# LIXIE_II.net
KiCad netlist of a schematic drawn in EAGLE
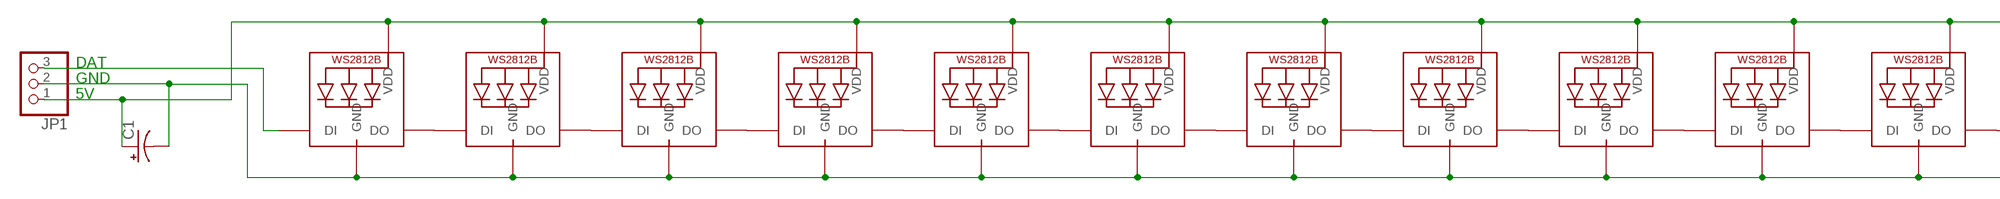
[diagram p0: schematic, sheet 1, part 1 of 2]
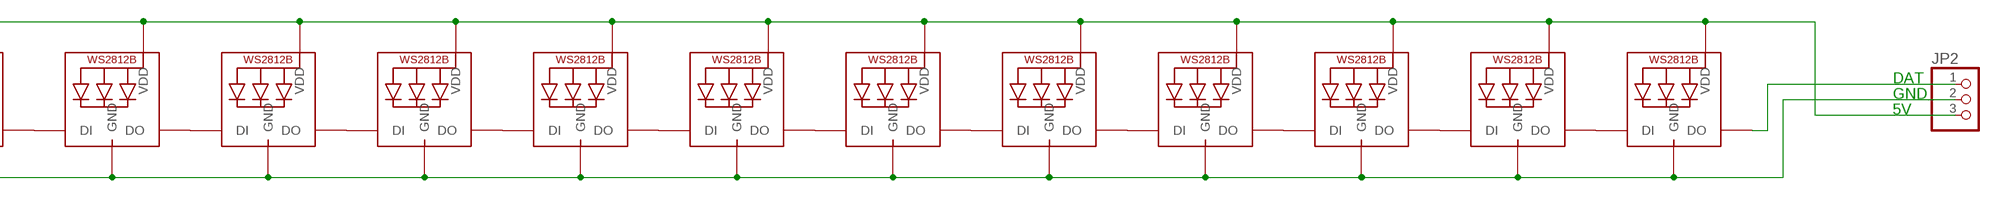
[diagram p1: schematic, sheet 1, part 2 of 2]

(export (version "E")
  (design (tool "Eeschema 10.0.6"))
  (components
    (comp (ref "C1")
      (value "CPOL-USE5-10.5")
      (footprint "eagle-import:E5-10,5")
      (libsource (lib "eagle-import") (part "CPOL-USE5-10.5"))
    )
    (comp (ref "JP1")
      (value "PINHD-1X3")
      (footprint "eagle-import:1X03")
      (libsource (lib "eagle-import") (part "PINHD-1X3"))
    )
    (comp (ref "JP2")
      (value "PINHD-1X3")
      (footprint "eagle-import:1X03")
      (libsource (lib "eagle-import") (part "PINHD-1X3"))
    )
    (comp (ref "LED1")
      (value "WS2812B_5050N")
      (footprint "eagle-import:WS2812B-NARROW")
      (libsource (lib "eagle-import") (part "WS2812B_5050N"))
    )
    (comp (ref "LED2")
      (value "WS2812B_5050N")
      (footprint "eagle-import:WS2812B-NARROW")
      (libsource (lib "eagle-import") (part "WS2812B_5050N"))
    )
    (comp (ref "LED3")
      (value "WS2812B_5050N")
      (footprint "eagle-import:WS2812B-NARROW")
      (libsource (lib "eagle-import") (part "WS2812B_5050N"))
    )
    (comp (ref "LED4")
      (value "WS2812B_5050N")
      (footprint "eagle-import:WS2812B-NARROW")
      (libsource (lib "eagle-import") (part "WS2812B_5050N"))
    )
    (comp (ref "LED5")
      (value "WS2812B_5050N")
      (footprint "eagle-import:WS2812B-NARROW")
      (libsource (lib "eagle-import") (part "WS2812B_5050N"))
    )
    (comp (ref "LED6")
      (value "WS2812B_5050N")
      (footprint "eagle-import:WS2812B-NARROW")
      (libsource (lib "eagle-import") (part "WS2812B_5050N"))
    )
    (comp (ref "LED7")
      (value "WS2812B_5050N")
      (footprint "eagle-import:WS2812B-NARROW")
      (libsource (lib "eagle-import") (part "WS2812B_5050N"))
    )
    (comp (ref "LED8")
      (value "WS2812B_5050N")
      (footprint "eagle-import:WS2812B-NARROW")
      (libsource (lib "eagle-import") (part "WS2812B_5050N"))
    )
    (comp (ref "LED9")
      (value "WS2812B_5050N")
      (footprint "eagle-import:WS2812B-NARROW")
      (libsource (lib "eagle-import") (part "WS2812B_5050N"))
    )
    (comp (ref "LED10")
      (value "WS2812B_5050N")
      (footprint "eagle-import:WS2812B-NARROW")
      (libsource (lib "eagle-import") (part "WS2812B_5050N"))
    )
    (comp (ref "LED11")
      (value "WS2812B_5050N")
      (footprint "eagle-import:WS2812B-NARROW")
      (libsource (lib "eagle-import") (part "WS2812B_5050N"))
    )
    (comp (ref "LED12")
      (value "WS2812B_5050N")
      (footprint "eagle-import:WS2812B-NARROW")
      (libsource (lib "eagle-import") (part "WS2812B_5050N"))
    )
    (comp (ref "LED13")
      (value "WS2812B_5050N")
      (footprint "eagle-import:WS2812B-NARROW")
      (libsource (lib "eagle-import") (part "WS2812B_5050N"))
    )
    (comp (ref "LED14")
      (value "WS2812B_5050N")
      (footprint "eagle-import:WS2812B-NARROW")
      (libsource (lib "eagle-import") (part "WS2812B_5050N"))
    )
    (comp (ref "LED15")
      (value "WS2812B_5050N")
      (footprint "eagle-import:WS2812B-NARROW")
      (libsource (lib "eagle-import") (part "WS2812B_5050N"))
    )
    (comp (ref "LED16")
      (value "WS2812B_5050N")
      (footprint "eagle-import:WS2812B-NARROW")
      (libsource (lib "eagle-import") (part "WS2812B_5050N"))
    )
    (comp (ref "LED17")
      (value "WS2812B_5050N")
      (footprint "eagle-import:WS2812B-NARROW")
      (libsource (lib "eagle-import") (part "WS2812B_5050N"))
    )
    (comp (ref "LED18")
      (value "WS2812B_5050N")
      (footprint "eagle-import:WS2812B-NARROW")
      (libsource (lib "eagle-import") (part "WS2812B_5050N"))
    )
    (comp (ref "LED19")
      (value "WS2812B_5050N")
      (footprint "eagle-import:WS2812B-NARROW")
      (libsource (lib "eagle-import") (part "WS2812B_5050N"))
    )
    (comp (ref "LED20")
      (value "WS2812B_5050N")
      (footprint "eagle-import:WS2812B-NARROW")
      (libsource (lib "eagle-import") (part "WS2812B_5050N"))
    )
    (comp (ref "LED21")
      (value "WS2812B_5050N")
      (footprint "eagle-import:WS2812B-NARROW")
      (libsource (lib "eagle-import") (part "WS2812B_5050N"))
    )
    (comp (ref "LED22")
      (value "WS2812B_5050N")
      (footprint "eagle-import:WS2812B-NARROW")
      (libsource (lib "eagle-import") (part "WS2812B_5050N"))
    )
  )
  (nets
    (net (code "1") (name "Net-(LED1-DI)") (class "Default")
      (node (ref "JP1") (pin "3") (pinfunction "3_3") (pintype "passive"))
      (node (ref "LED1") (pin "4-DIN") (pinfunction "DI_4-DIN") (pintype "input"))
    )
    (net (code "2") (name "Net-(LED1-DO)") (class "Default")
      (node (ref "LED1") (pin "2-DOUT") (pinfunction "DO_2-DOUT") (pintype "output"))
      (node (ref "LED2") (pin "4-DIN") (pinfunction "DI_4-DIN") (pintype "input"))
    )
    (net (code "3") (name "Net-(LED1-GND)") (class "Default")
      (node (ref "C1") (pin "-") (pinfunction "-_-") (pintype "passive"))
      (node (ref "JP1") (pin "2") (pinfunction "2_2") (pintype "passive"))
      (node (ref "JP2") (pin "2") (pinfunction "2_2") (pintype "passive"))
      (node (ref "LED1") (pin "3-GND") (pinfunction "GND_3-GND") (pintype "power_in"))
      (node (ref "LED10") (pin "3-GND") (pinfunction "GND_3-GND") (pintype "power_in"))
      (node (ref "LED11") (pin "3-GND") (pinfunction "GND_3-GND") (pintype "power_in"))
      (node (ref "LED12") (pin "3-GND") (pinfunction "GND_3-GND") (pintype "power_in"))
      (node (ref "LED13") (pin "3-GND") (pinfunction "GND_3-GND") (pintype "power_in"))
      (node (ref "LED14") (pin "3-GND") (pinfunction "GND_3-GND") (pintype "power_in"))
      (node (ref "LED15") (pin "3-GND") (pinfunction "GND_3-GND") (pintype "power_in"))
      (node (ref "LED16") (pin "3-GND") (pinfunction "GND_3-GND") (pintype "power_in"))
      (node (ref "LED17") (pin "3-GND") (pinfunction "GND_3-GND") (pintype "power_in"))
      (node (ref "LED18") (pin "3-GND") (pinfunction "GND_3-GND") (pintype "power_in"))
      (node (ref "LED19") (pin "3-GND") (pinfunction "GND_3-GND") (pintype "power_in"))
      (node (ref "LED2") (pin "3-GND") (pinfunction "GND_3-GND") (pintype "power_in"))
      (node (ref "LED20") (pin "3-GND") (pinfunction "GND_3-GND") (pintype "power_in"))
      (node (ref "LED21") (pin "3-GND") (pinfunction "GND_3-GND") (pintype "power_in"))
      (node (ref "LED22") (pin "3-GND") (pinfunction "GND_3-GND") (pintype "power_in"))
      (node (ref "LED3") (pin "3-GND") (pinfunction "GND_3-GND") (pintype "power_in"))
      (node (ref "LED4") (pin "3-GND") (pinfunction "GND_3-GND") (pintype "power_in"))
      (node (ref "LED5") (pin "3-GND") (pinfunction "GND_3-GND") (pintype "power_in"))
      (node (ref "LED6") (pin "3-GND") (pinfunction "GND_3-GND") (pintype "power_in"))
      (node (ref "LED7") (pin "3-GND") (pinfunction "GND_3-GND") (pintype "power_in"))
      (node (ref "LED8") (pin "3-GND") (pinfunction "GND_3-GND") (pintype "power_in"))
      (node (ref "LED9") (pin "3-GND") (pinfunction "GND_3-GND") (pintype "power_in"))
    )
    (net (code "4") (name "Net-(LED1-VDD)") (class "Default")
      (node (ref "C1") (pin "+") (pinfunction "+_+") (pintype "passive"))
      (node (ref "JP1") (pin "1") (pinfunction "1_1") (pintype "passive"))
      (node (ref "JP2") (pin "3") (pinfunction "3_3") (pintype "passive"))
      (node (ref "LED1") (pin "1-VDD") (pinfunction "VDD_1-VDD") (pintype "power_in"))
      (node (ref "LED10") (pin "1-VDD") (pinfunction "VDD_1-VDD") (pintype "power_in"))
      (node (ref "LED11") (pin "1-VDD") (pinfunction "VDD_1-VDD") (pintype "power_in"))
      (node (ref "LED12") (pin "1-VDD") (pinfunction "VDD_1-VDD") (pintype "power_in"))
      (node (ref "LED13") (pin "1-VDD") (pinfunction "VDD_1-VDD") (pintype "power_in"))
      (node (ref "LED14") (pin "1-VDD") (pinfunction "VDD_1-VDD") (pintype "power_in"))
      (node (ref "LED15") (pin "1-VDD") (pinfunction "VDD_1-VDD") (pintype "power_in"))
      (node (ref "LED16") (pin "1-VDD") (pinfunction "VDD_1-VDD") (pintype "power_in"))
      (node (ref "LED17") (pin "1-VDD") (pinfunction "VDD_1-VDD") (pintype "power_in"))
      (node (ref "LED18") (pin "1-VDD") (pinfunction "VDD_1-VDD") (pintype "power_in"))
      (node (ref "LED19") (pin "1-VDD") (pinfunction "VDD_1-VDD") (pintype "power_in"))
      (node (ref "LED2") (pin "1-VDD") (pinfunction "VDD_1-VDD") (pintype "power_in"))
      (node (ref "LED20") (pin "1-VDD") (pinfunction "VDD_1-VDD") (pintype "power_in"))
      (node (ref "LED21") (pin "1-VDD") (pinfunction "VDD_1-VDD") (pintype "power_in"))
      (node (ref "LED22") (pin "1-VDD") (pinfunction "VDD_1-VDD") (pintype "power_in"))
      (node (ref "LED3") (pin "1-VDD") (pinfunction "VDD_1-VDD") (pintype "power_in"))
      (node (ref "LED4") (pin "1-VDD") (pinfunction "VDD_1-VDD") (pintype "power_in"))
      (node (ref "LED5") (pin "1-VDD") (pinfunction "VDD_1-VDD") (pintype "power_in"))
      (node (ref "LED6") (pin "1-VDD") (pinfunction "VDD_1-VDD") (pintype "power_in"))
      (node (ref "LED7") (pin "1-VDD") (pinfunction "VDD_1-VDD") (pintype "power_in"))
      (node (ref "LED8") (pin "1-VDD") (pinfunction "VDD_1-VDD") (pintype "power_in"))
      (node (ref "LED9") (pin "1-VDD") (pinfunction "VDD_1-VDD") (pintype "power_in"))
    )
    (net (code "5") (name "Net-(LED2-DO)") (class "Default")
      (node (ref "LED2") (pin "2-DOUT") (pinfunction "DO_2-DOUT") (pintype "output"))
      (node (ref "LED3") (pin "4-DIN") (pinfunction "DI_4-DIN") (pintype "input"))
    )
    (net (code "6") (name "Net-(LED3-DO)") (class "Default")
      (node (ref "LED3") (pin "2-DOUT") (pinfunction "DO_2-DOUT") (pintype "output"))
      (node (ref "LED4") (pin "4-DIN") (pinfunction "DI_4-DIN") (pintype "input"))
    )
    (net (code "7") (name "Net-(LED4-DO)") (class "Default")
      (node (ref "LED4") (pin "2-DOUT") (pinfunction "DO_2-DOUT") (pintype "output"))
      (node (ref "LED5") (pin "4-DIN") (pinfunction "DI_4-DIN") (pintype "input"))
    )
    (net (code "8") (name "Net-(LED5-DO)") (class "Default")
      (node (ref "LED5") (pin "2-DOUT") (pinfunction "DO_2-DOUT") (pintype "output"))
      (node (ref "LED6") (pin "4-DIN") (pinfunction "DI_4-DIN") (pintype "input"))
    )
    (net (code "9") (name "Net-(LED6-DO)") (class "Default")
      (node (ref "LED6") (pin "2-DOUT") (pinfunction "DO_2-DOUT") (pintype "output"))
      (node (ref "LED7") (pin "4-DIN") (pinfunction "DI_4-DIN") (pintype "input"))
    )
    (net (code "10") (name "Net-(LED7-DO)") (class "Default")
      (node (ref "LED7") (pin "2-DOUT") (pinfunction "DO_2-DOUT") (pintype "output"))
      (node (ref "LED8") (pin "4-DIN") (pinfunction "DI_4-DIN") (pintype "input"))
    )
    (net (code "11") (name "Net-(LED8-DO)") (class "Default")
      (node (ref "LED8") (pin "2-DOUT") (pinfunction "DO_2-DOUT") (pintype "output"))
      (node (ref "LED9") (pin "4-DIN") (pinfunction "DI_4-DIN") (pintype "input"))
    )
    (net (code "12") (name "Net-(LED10-DI)") (class "Default")
      (node (ref "LED10") (pin "4-DIN") (pinfunction "DI_4-DIN") (pintype "input"))
      (node (ref "LED9") (pin "2-DOUT") (pinfunction "DO_2-DOUT") (pintype "output"))
    )
    (net (code "13") (name "Net-(LED10-DO)") (class "Default")
      (node (ref "LED10") (pin "2-DOUT") (pinfunction "DO_2-DOUT") (pintype "output"))
      (node (ref "LED11") (pin "4-DIN") (pinfunction "DI_4-DIN") (pintype "input"))
    )
    (net (code "14") (name "Net-(LED11-DO)") (class "Default")
      (node (ref "LED11") (pin "2-DOUT") (pinfunction "DO_2-DOUT") (pintype "output"))
      (node (ref "LED12") (pin "4-DIN") (pinfunction "DI_4-DIN") (pintype "input"))
    )
    (net (code "15") (name "Net-(LED12-DO)") (class "Default")
      (node (ref "LED12") (pin "2-DOUT") (pinfunction "DO_2-DOUT") (pintype "output"))
      (node (ref "LED13") (pin "4-DIN") (pinfunction "DI_4-DIN") (pintype "input"))
    )
    (net (code "16") (name "Net-(LED13-DO)") (class "Default")
      (node (ref "LED13") (pin "2-DOUT") (pinfunction "DO_2-DOUT") (pintype "output"))
      (node (ref "LED14") (pin "4-DIN") (pinfunction "DI_4-DIN") (pintype "input"))
    )
    (net (code "17") (name "Net-(LED14-DO)") (class "Default")
      (node (ref "LED14") (pin "2-DOUT") (pinfunction "DO_2-DOUT") (pintype "output"))
      (node (ref "LED15") (pin "4-DIN") (pinfunction "DI_4-DIN") (pintype "input"))
    )
    (net (code "18") (name "Net-(LED15-DO)") (class "Default")
      (node (ref "LED15") (pin "2-DOUT") (pinfunction "DO_2-DOUT") (pintype "output"))
      (node (ref "LED16") (pin "4-DIN") (pinfunction "DI_4-DIN") (pintype "input"))
    )
    (net (code "19") (name "Net-(LED16-DO)") (class "Default")
      (node (ref "LED16") (pin "2-DOUT") (pinfunction "DO_2-DOUT") (pintype "output"))
      (node (ref "LED17") (pin "4-DIN") (pinfunction "DI_4-DIN") (pintype "input"))
    )
    (net (code "20") (name "Net-(LED17-DO)") (class "Default")
      (node (ref "LED17") (pin "2-DOUT") (pinfunction "DO_2-DOUT") (pintype "output"))
      (node (ref "LED18") (pin "4-DIN") (pinfunction "DI_4-DIN") (pintype "input"))
    )
    (net (code "21") (name "Net-(LED18-DO)") (class "Default")
      (node (ref "LED18") (pin "2-DOUT") (pinfunction "DO_2-DOUT") (pintype "output"))
      (node (ref "LED19") (pin "4-DIN") (pinfunction "DI_4-DIN") (pintype "input"))
    )
    (net (code "22") (name "Net-(LED19-DO)") (class "Default")
      (node (ref "LED19") (pin "2-DOUT") (pinfunction "DO_2-DOUT") (pintype "output"))
      (node (ref "LED20") (pin "4-DIN") (pinfunction "DI_4-DIN") (pintype "input"))
    )
    (net (code "23") (name "Net-(LED20-DO)") (class "Default")
      (node (ref "LED20") (pin "2-DOUT") (pinfunction "DO_2-DOUT") (pintype "output"))
      (node (ref "LED21") (pin "4-DIN") (pinfunction "DI_4-DIN") (pintype "input"))
    )
    (net (code "24") (name "Net-(LED21-DO)") (class "Default")
      (node (ref "LED21") (pin "2-DOUT") (pinfunction "DO_2-DOUT") (pintype "output"))
      (node (ref "LED22") (pin "4-DIN") (pinfunction "DI_4-DIN") (pintype "input"))
    )
    (net (code "25") (name "Net-(LED22-DO)") (class "Default")
      (node (ref "JP2") (pin "1") (pinfunction "1_1") (pintype "passive"))
      (node (ref "LED22") (pin "2-DOUT") (pinfunction "DO_2-DOUT") (pintype "output"))
    )
  )
)
